# untitled.net
KiCad netlist of a schematic drawn in EAGLE
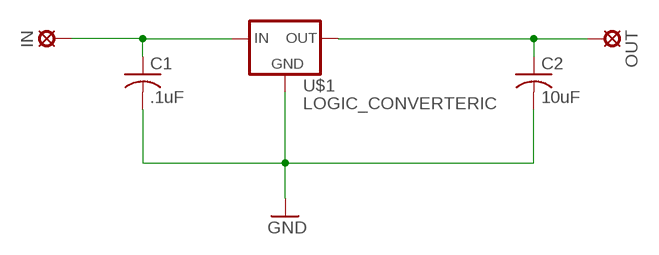
[diagram p0: schematic, sheet 1]

(export (version "E")
  (design (tool "Eeschema 10.0.6"))
  (components
    (comp (ref "C1")
      (value ".1uF")
      (footprint "eagle-import:C0805K")
      (libsource (lib "eagle-import") (part "C-USC0805K"))
    )
    (comp (ref "C2")
      (value "10uF")
      (footprint "eagle-import:C0805K")
      (libsource (lib "eagle-import") (part "C-USC0805K"))
    )
    (comp (ref "IN")
      (value "LSP10")
      (footprint "eagle-import:LSP10")
      (libsource (lib "eagle-import") (part "LSP10"))
    )
    (comp (ref "OUT")
      (value "LSP10")
      (footprint "eagle-import:LSP10")
      (libsource (lib "eagle-import") (part "LSP10"))
    )
    (comp (ref "U$1")
      (value "LOGIC_CONVERTERIC")
      (footprint "eagle-import:SOT223")
      (libsource (lib "eagle-import") (part "LOGIC_CONVERTERIC"))
    )
  )
  (nets
    (net (code "1") (name "GND") (class "Default")
      (node (ref "C1") (pin "2") (pinfunction "2_2") (pintype "passive"))
      (node (ref "C2") (pin "2") (pinfunction "2_2") (pintype "passive"))
      (node (ref "U$1") (pin "GND") (pinfunction "GND_GND") (pintype "input"))
    )
    (net (code "2") (name "Net-(C1-Pad1)") (class "Default")
      (node (ref "C1") (pin "1") (pinfunction "1_1") (pintype "passive"))
      (node (ref "IN") (pin "MP") (pinfunction "MP_MP") (pintype "passive"))
      (node (ref "U$1") (pin "IN") (pinfunction "IN_IN") (pintype "input"))
    )
    (net (code "3") (name "Net-(C2-Pad1)") (class "Default")
      (node (ref "C2") (pin "1") (pinfunction "1_1") (pintype "passive"))
      (node (ref "OUT") (pin "MP") (pinfunction "MP_MP") (pintype "passive"))
      (node (ref "U$1") (pin "OUT") (pinfunction "OUT_OUT") (pintype "passive"))
    )
  )
)
